# MB_RELAY.net
KiCad netlist of a schematic drawn in Altium Designer
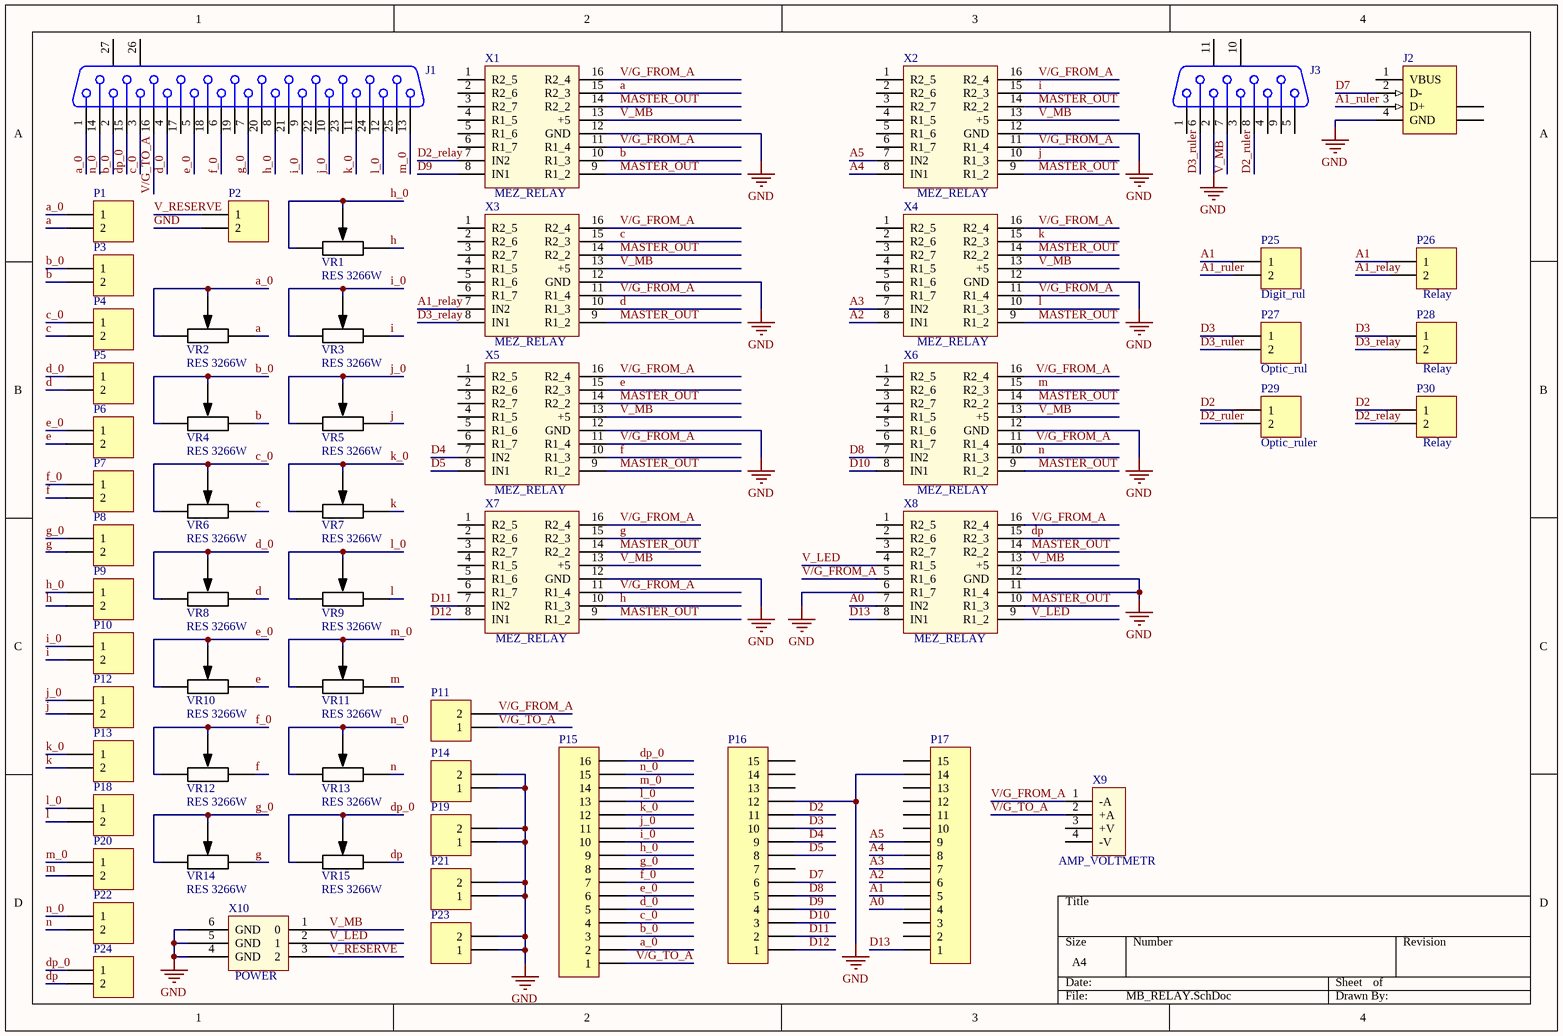
[diagram p0: MB_RELAY.SchDoc]

(export (version "E")
  (design (tool "Eeschema 10.0.6"))
  (components
    (comp (ref "J1")
      (value "D Connector 25")
      (footprint "DSUB1.385-2H25A")
      (description "Receptacle Assembly, 25 Position, Right Angle")
      (fields (field (name "PUBLISHER") "Altium Limited"))
      (libsource (lib "Miscellaneous Connectors") (part "D Connector 25"))
    )
    (comp (ref "J2")
      (value "1-353576-1")
      (footprint "353576")
      (description "USB 1.1, Right Angle, SMT, A Type, Receptacle, 4 Position, White")
      (fields (field (name "PUBLISHER") "Altium Limited"))
      (libsource (lib "AMP Serial Bus USB") (part "1-353576-1"))
    )
    (comp (ref "J3")
      (value "D Connector 9")
      (footprint "DSUB1.385-2H9")
      (description "Receptacle Assembly, 9 Position, Right Angle")
      (fields (field (name "PUBLISHER") "Altium Limited"))
      (libsource (lib "Miscellaneous Connectors") (part "D Connector 9"))
    )
    (comp (ref "P1")
      (value "Header 2")
      (footprint "HDR1X2")
      (description "Header, 2-Pin")
      (fields (field (name "PUBLISHER") "Altium Limited"))
      (libsource (lib "Miscellaneous Connectors") (part "Header 2"))
    )
    (comp (ref "P2")
      (value "Header 2")
      (footprint "HDR1X2")
      (description "Header, 2-Pin")
      (fields (field (name "PUBLISHER") "Altium Limited"))
      (libsource (lib "Miscellaneous Connectors") (part "Header 2"))
    )
    (comp (ref "P3")
      (value "Header 2")
      (footprint "HDR1X2")
      (description "Header, 2-Pin")
      (fields (field (name "PUBLISHER") "Altium Limited"))
      (libsource (lib "Miscellaneous Connectors") (part "Header 2"))
    )
    (comp (ref "P4")
      (value "Header 2")
      (footprint "HDR1X2")
      (description "Header, 2-Pin")
      (fields (field (name "PUBLISHER") "Altium Limited"))
      (libsource (lib "Miscellaneous Connectors") (part "Header 2"))
    )
    (comp (ref "P5")
      (value "Header 2")
      (footprint "HDR1X2")
      (description "Header, 2-Pin")
      (fields (field (name "PUBLISHER") "Altium Limited"))
      (libsource (lib "Miscellaneous Connectors") (part "Header 2"))
    )
    (comp (ref "P6")
      (value "GND")
      (footprint "HDR1X2")
      (description "Header, 2-Pin")
      (fields (field (name "PUBLISHER") "Altium Limited"))
      (libsource (lib "Miscellaneous Connectors") (part "Header 2"))
    )
    (comp (ref "P7")
      (value "GND")
      (footprint "HDR1X2")
      (description "Header, 2-Pin")
      (fields (field (name "PUBLISHER") "Altium Limited"))
      (libsource (lib "Miscellaneous Connectors") (part "Header 2"))
    )
    (comp (ref "P8")
      (value "GND")
      (footprint "HDR1X2")
      (description "Header, 2-Pin")
      (fields (field (name "PUBLISHER") "Altium Limited"))
      (libsource (lib "Miscellaneous Connectors") (part "Header 2"))
    )
    (comp (ref "P9")
      (value "GND")
      (footprint "HDR1X2")
      (description "Header, 2-Pin")
      (fields (field (name "PUBLISHER") "Altium Limited"))
      (libsource (lib "Miscellaneous Connectors") (part "Header 2"))
    )
    (comp (ref "P10")
      (value "Header 2")
      (footprint "HDR1X2")
      (description "Header, 2-Pin")
      (fields (field (name "PUBLISHER") "Altium Limited"))
      (libsource (lib "Miscellaneous Connectors") (part "Header 2"))
    )
    (comp (ref "P11")
      (value "Header 2")
      (footprint "HDR1X2")
      (description "Header, 2-Pin")
      (fields (field (name "PUBLISHER") "Altium Limited"))
      (libsource (lib "") (part "Header 2_1"))
    )
    (comp (ref "P12")
      (value "Header 2")
      (footprint "HDR1X2")
      (description "Header, 2-Pin")
      (fields (field (name "PUBLISHER") "Altium Limited"))
      (libsource (lib "Miscellaneous Connectors") (part "Header 2"))
    )
    (comp (ref "P13")
      (value "GND")
      (footprint "HDR1X2")
      (description "Header, 2-Pin")
      (fields (field (name "PUBLISHER") "Altium Limited"))
      (libsource (lib "Miscellaneous Connectors") (part "Header 2"))
    )
    (comp (ref "P14")
      (value "GND")
      (footprint "HDR1X2")
      (description "Header, 2-Pin")
      (fields (field (name "PUBLISHER") "Altium Limited"))
      (libsource (lib "") (part "Header 2_1"))
    )
    (comp (ref "P15")
      (value "Header 16")
      (footprint "HDR1X16")
      (description "Header, 16-Pin")
      (fields (field (name "PUBLISHER") "Altium Limited"))
      (libsource (lib "Miscellaneous Connectors") (part "Header 16"))
    )
    (comp (ref "P16")
      (value "Header 15")
      (footprint "HDR1X15")
      (description "Header, 15-Pin")
      (fields (field (name "PUBLISHER") "Altium Limited"))
      (libsource (lib "Miscellaneous Connectors") (part "Header 15"))
    )
    (comp (ref "P17")
      (value "Header 15")
      (footprint "HDR1X15")
      (description "Header, 15-Pin")
      (fields (field (name "PUBLISHER") "Altium Limited"))
      (libsource (lib "") (part "Header 15_1"))
    )
    (comp (ref "P18")
      (value "GND")
      (footprint "HDR1X2")
      (description "Header, 2-Pin")
      (fields (field (name "PUBLISHER") "Altium Limited"))
      (libsource (lib "Miscellaneous Connectors") (part "Header 2"))
    )
    (comp (ref "P19")
      (value "GND")
      (footprint "HDR1X2")
      (description "Header, 2-Pin")
      (fields (field (name "PUBLISHER") "Altium Limited"))
      (libsource (lib "") (part "Header 2_1"))
    )
    (comp (ref "P20")
      (value "GND")
      (footprint "HDR1X2")
      (description "Header, 2-Pin")
      (fields (field (name "PUBLISHER") "Altium Limited"))
      (libsource (lib "Miscellaneous Connectors") (part "Header 2"))
    )
    (comp (ref "P21")
      (value "GND")
      (footprint "HDR1X2")
      (description "Header, 2-Pin")
      (fields (field (name "PUBLISHER") "Altium Limited"))
      (libsource (lib "") (part "Header 2_1"))
    )
    (comp (ref "P22")
      (value "GND")
      (footprint "HDR1X2")
      (description "Header, 2-Pin")
      (fields (field (name "PUBLISHER") "Altium Limited"))
      (libsource (lib "Miscellaneous Connectors") (part "Header 2"))
    )
    (comp (ref "P23")
      (value "GND")
      (footprint "HDR1X2")
      (description "Header, 2-Pin")
      (fields (field (name "PUBLISHER") "Altium Limited"))
      (libsource (lib "") (part "Header 2_1"))
    )
    (comp (ref "P24")
      (value "GND")
      (footprint "HDR1X2")
      (description "Header, 2-Pin")
      (fields (field (name "PUBLISHER") "Altium Limited"))
      (libsource (lib "Miscellaneous Connectors") (part "Header 2"))
    )
    (comp (ref "P25")
      (value "Digit_rul")
      (footprint "HDR1X2")
      (description "Header, 2-Pin")
      (fields (field (name "PUBLISHER") "Altium Limited"))
      (libsource (lib "Miscellaneous Connectors") (part "Header 2"))
    )
    (comp (ref "P26")
      (value "Relay")
      (footprint "HDR1X2")
      (description "Header, 2-Pin")
      (fields (field (name "PUBLISHER") "Altium Limited"))
      (libsource (lib "Miscellaneous Connectors") (part "Header 2"))
    )
    (comp (ref "P27")
      (value "Optic_rul")
      (footprint "HDR1X2")
      (description "Header, 2-Pin")
      (fields (field (name "PUBLISHER") "Altium Limited"))
      (libsource (lib "Miscellaneous Connectors") (part "Header 2"))
    )
    (comp (ref "P28")
      (value "Relay")
      (footprint "HDR1X2")
      (description "Header, 2-Pin")
      (fields (field (name "PUBLISHER") "Altium Limited"))
      (libsource (lib "Miscellaneous Connectors") (part "Header 2"))
    )
    (comp (ref "P29")
      (value "Optic_ruler")
      (footprint "HDR1X2")
      (description "Header, 2-Pin")
      (fields (field (name "PUBLISHER") "Altium Limited"))
      (libsource (lib "Miscellaneous Connectors") (part "Header 2"))
    )
    (comp (ref "P30")
      (value "Relay")
      (footprint "HDR1X2")
      (description "Header, 2-Pin")
      (fields (field (name "PUBLISHER") "Altium Limited"))
      (libsource (lib "Miscellaneous Connectors") (part "Header 2"))
    )
    (comp (ref "VR1")
      (value "RES 3266W")
      (footprint "aab_Passive:RES 3266W")
      (libsource (lib "aab_Schlib") (part "RES 3266W"))
    )
    (comp (ref "VR2")
      (value "RES 3266W")
      (footprint "aab_Passive:RES 3266W")
      (libsource (lib "aab_Schlib") (part "RES 3266W"))
    )
    (comp (ref "VR3")
      (value "RES 3266W")
      (footprint "aab_Passive:RES 3266W")
      (libsource (lib "aab_Schlib") (part "RES 3266W"))
    )
    (comp (ref "VR4")
      (value "RES 3266W")
      (footprint "aab_Passive:RES 3266W")
      (libsource (lib "aab_Schlib") (part "RES 3266W"))
    )
    (comp (ref "VR5")
      (value "RES 3266W")
      (footprint "aab_Passive:RES 3266W")
      (libsource (lib "aab_Schlib") (part "RES 3266W"))
    )
    (comp (ref "VR6")
      (value "RES 3266W")
      (footprint "aab_Passive:RES 3266W")
      (libsource (lib "aab_Schlib") (part "RES 3266W"))
    )
    (comp (ref "VR7")
      (value "RES 3266W")
      (footprint "aab_Passive:RES 3266W")
      (libsource (lib "aab_Schlib") (part "RES 3266W"))
    )
    (comp (ref "VR8")
      (value "RES 3266W")
      (footprint "aab_Passive:RES 3266W")
      (libsource (lib "aab_Schlib") (part "RES 3266W"))
    )
    (comp (ref "VR9")
      (value "RES 3266W")
      (footprint "aab_Passive:RES 3266W")
      (libsource (lib "aab_Schlib") (part "RES 3266W"))
    )
    (comp (ref "VR10")
      (value "RES 3266W")
      (footprint "aab_Passive:RES 3266W")
      (libsource (lib "aab_Schlib") (part "RES 3266W"))
    )
    (comp (ref "VR11")
      (value "RES 3266W")
      (footprint "aab_Passive:RES 3266W")
      (libsource (lib "aab_Schlib") (part "RES 3266W"))
    )
    (comp (ref "VR12")
      (value "RES 3266W")
      (footprint "aab_Passive:RES 3266W")
      (libsource (lib "aab_Schlib") (part "RES 3266W"))
    )
    (comp (ref "VR13")
      (value "RES 3266W")
      (footprint "aab_Passive:RES 3266W")
      (libsource (lib "aab_Schlib") (part "RES 3266W"))
    )
    (comp (ref "VR14")
      (value "RES 3266W")
      (footprint "aab_Passive:RES 3266W")
      (libsource (lib "aab_Schlib") (part "RES 3266W"))
    )
    (comp (ref "VR15")
      (value "RES 3266W")
      (footprint "aab_Passive:RES 3266W")
      (libsource (lib "aab_Schlib") (part "RES 3266W"))
    )
    (comp (ref "X1")
      (value "MEZ_RELAY")
      (footprint "MEZ_RELAY")
      (libsource (lib "msp_SchLib") (part "MEZ_RELAY"))
    )
    (comp (ref "X2")
      (value "MEZ_RELAY")
      (footprint "MEZ_RELAY")
      (libsource (lib "msp_SchLib") (part "MEZ_RELAY"))
    )
    (comp (ref "X3")
      (value "MEZ_RELAY")
      (footprint "MEZ_RELAY")
      (libsource (lib "msp_SchLib") (part "MEZ_RELAY"))
    )
    (comp (ref "X4")
      (value "MEZ_RELAY")
      (footprint "MEZ_RELAY")
      (libsource (lib "msp_SchLib") (part "MEZ_RELAY"))
    )
    (comp (ref "X5")
      (value "MEZ_RELAY")
      (footprint "MEZ_RELAY")
      (libsource (lib "msp_SchLib") (part "MEZ_RELAY"))
    )
    (comp (ref "X6")
      (value "MEZ_RELAY")
      (footprint "MEZ_RELAY")
      (libsource (lib "msp_SchLib") (part "MEZ_RELAY"))
    )
    (comp (ref "X7")
      (value "MEZ_RELAY")
      (footprint "MEZ_RELAY")
      (libsource (lib "msp_SchLib") (part "MEZ_RELAY"))
    )
    (comp (ref "X8")
      (value "MEZ_RELAY")
      (footprint "MEZ_RELAY")
      (libsource (lib "msp_SchLib") (part "MEZ_RELAY"))
    )
    (comp (ref "X9")
      (value "AMP_VOLTMETR")
      (footprint "vpl_Passive:AMP_VOLTMETER")
      (libsource (lib "msp_SchLib") (part "AMP_VOLTMETR"))
    )
    (comp (ref "X10")
      (value "POWER")
      (footprint "vpl_Passive:POWER")
      (libsource (lib "msp_SchLib") (part "POWER"))
    )
  )
  (nets
    (net (code "1") (name "/A0") (class "Default")
      (node (ref "P17") (pin "4") (pinfunction "4_4") (pintype "passive"))
      (node (ref "X8") (pin "7") (pinfunction "IN2_7") (pintype "passive"))
    )
    (net (code "2") (name "/A1") (class "Default")
      (node (ref "P17") (pin "5") (pinfunction "5_5") (pintype "passive"))
      (node (ref "P25") (pin "1") (pinfunction "1_1") (pintype "passive"))
      (node (ref "P26") (pin "1") (pinfunction "1_1") (pintype "passive"))
    )
    (net (code "3") (name "/A1_relay") (class "Default")
      (node (ref "P26") (pin "2") (pinfunction "2_2") (pintype "passive"))
      (node (ref "X3") (pin "7") (pinfunction "IN2_7") (pintype "passive"))
    )
    (net (code "4") (name "/A1_ruler") (class "Default")
      (node (ref "J2") (pin "3") (pinfunction "D+_3") (pintype "input"))
      (node (ref "P25") (pin "2") (pinfunction "2_2") (pintype "passive"))
    )
    (net (code "5") (name "/A2") (class "Default")
      (node (ref "P17") (pin "6") (pinfunction "6_6") (pintype "passive"))
      (node (ref "X4") (pin "8") (pinfunction "IN1_8") (pintype "passive"))
    )
    (net (code "6") (name "/A3") (class "Default")
      (node (ref "P17") (pin "7") (pinfunction "7_7") (pintype "passive"))
      (node (ref "X4") (pin "7") (pinfunction "IN2_7") (pintype "passive"))
    )
    (net (code "7") (name "/A4") (class "Default")
      (node (ref "P17") (pin "8") (pinfunction "8_8") (pintype "passive"))
      (node (ref "X2") (pin "8") (pinfunction "IN1_8") (pintype "passive"))
    )
    (net (code "8") (name "/A5") (class "Default")
      (node (ref "P17") (pin "9") (pinfunction "9_9") (pintype "passive"))
      (node (ref "X2") (pin "7") (pinfunction "IN2_7") (pintype "passive"))
    )
    (net (code "9") (name "/D2") (class "Default")
      (node (ref "P16") (pin "11") (pinfunction "11_11") (pintype "passive"))
      (node (ref "P29") (pin "1") (pinfunction "1_1") (pintype "passive"))
      (node (ref "P30") (pin "1") (pinfunction "1_1") (pintype "passive"))
    )
    (net (code "10") (name "/D2_relay") (class "Default")
      (node (ref "P30") (pin "2") (pinfunction "2_2") (pintype "passive"))
      (node (ref "X1") (pin "7") (pinfunction "IN2_7") (pintype "passive"))
    )
    (net (code "11") (name "/D2_ruler") (class "Default")
      (node (ref "J3") (pin "8") (pinfunction "8_8") (pintype "passive"))
      (node (ref "P29") (pin "2") (pinfunction "2_2") (pintype "passive"))
    )
    (net (code "12") (name "/D3") (class "Default")
      (node (ref "P16") (pin "10") (pinfunction "10_10") (pintype "passive"))
      (node (ref "P27") (pin "1") (pinfunction "1_1") (pintype "passive"))
      (node (ref "P28") (pin "1") (pinfunction "1_1") (pintype "passive"))
    )
    (net (code "13") (name "/D3_relay") (class "Default")
      (node (ref "P28") (pin "2") (pinfunction "2_2") (pintype "passive"))
      (node (ref "X3") (pin "8") (pinfunction "IN1_8") (pintype "passive"))
    )
    (net (code "14") (name "/D3_ruler") (class "Default")
      (node (ref "J3") (pin "6") (pinfunction "6_6") (pintype "passive"))
      (node (ref "P27") (pin "2") (pinfunction "2_2") (pintype "passive"))
    )
    (net (code "15") (name "/D4") (class "Default")
      (node (ref "P16") (pin "9") (pinfunction "9_9") (pintype "passive"))
      (node (ref "X5") (pin "7") (pinfunction "IN2_7") (pintype "passive"))
    )
    (net (code "16") (name "/D5") (class "Default")
      (node (ref "P16") (pin "8") (pinfunction "8_8") (pintype "passive"))
      (node (ref "X5") (pin "8") (pinfunction "IN1_8") (pintype "passive"))
    )
    (net (code "17") (name "/D7") (class "Default")
      (node (ref "J2") (pin "2") (pinfunction "D-_2") (pintype "input"))
      (node (ref "P16") (pin "6") (pinfunction "6_6") (pintype "passive"))
    )
    (net (code "18") (name "/D8") (class "Default")
      (node (ref "P16") (pin "5") (pinfunction "5_5") (pintype "passive"))
      (node (ref "X6") (pin "7") (pinfunction "IN2_7") (pintype "passive"))
    )
    (net (code "19") (name "/D9") (class "Default")
      (node (ref "P16") (pin "4") (pinfunction "4_4") (pintype "passive"))
      (node (ref "X1") (pin "8") (pinfunction "IN1_8") (pintype "passive"))
    )
    (net (code "20") (name "/D10") (class "Default")
      (node (ref "P16") (pin "3") (pinfunction "3_3") (pintype "passive"))
      (node (ref "X6") (pin "8") (pinfunction "IN1_8") (pintype "passive"))
    )
    (net (code "21") (name "/D11") (class "Default")
      (node (ref "P16") (pin "2") (pinfunction "2_2") (pintype "passive"))
      (node (ref "X7") (pin "7") (pinfunction "IN2_7") (pintype "passive"))
    )
    (net (code "22") (name "/D12") (class "Default")
      (node (ref "P16") (pin "1") (pinfunction "1_1") (pintype "passive"))
      (node (ref "X7") (pin "8") (pinfunction "IN1_8") (pintype "passive"))
    )
    (net (code "23") (name "/D13") (class "Default")
      (node (ref "P17") (pin "1") (pinfunction "1_1") (pintype "passive"))
      (node (ref "X8") (pin "8") (pinfunction "IN1_8") (pintype "passive"))
    )
    (net (code "24") (name "/MASTER_OUT") (class "Default")
      (node (ref "X1") (pin "14") (pinfunction "R2_2_14") (pintype "passive"))
      (node (ref "X1") (pin "9") (pinfunction "R1_2_9") (pintype "passive"))
      (node (ref "X2") (pin "14") (pinfunction "R2_2_14") (pintype "passive"))
      (node (ref "X2") (pin "9") (pinfunction "R1_2_9") (pintype "passive"))
      (node (ref "X3") (pin "14") (pinfunction "R2_2_14") (pintype "passive"))
      (node (ref "X3") (pin "9") (pinfunction "R1_2_9") (pintype "passive"))
      (node (ref "X4") (pin "14") (pinfunction "R2_2_14") (pintype "passive"))
      (node (ref "X4") (pin "9") (pinfunction "R1_2_9") (pintype "passive"))
      (node (ref "X5") (pin "14") (pinfunction "R2_2_14") (pintype "passive"))
      (node (ref "X5") (pin "9") (pinfunction "R1_2_9") (pintype "passive"))
      (node (ref "X6") (pin "14") (pinfunction "R2_2_14") (pintype "passive"))
      (node (ref "X6") (pin "9") (pinfunction "R1_2_9") (pintype "passive"))
      (node (ref "X7") (pin "14") (pinfunction "R2_2_14") (pintype "passive"))
      (node (ref "X7") (pin "9") (pinfunction "R1_2_9") (pintype "passive"))
      (node (ref "X8") (pin "10") (pinfunction "R1_3_10") (pintype "passive"))
      (node (ref "X8") (pin "14") (pinfunction "R2_2_14") (pintype "passive"))
    )
    (net (code "25") (name "/V_LED") (class "Default")
      (node (ref "X10") (pin "2") (pinfunction "1_2") (pintype "passive"))
      (node (ref "X8") (pin "4") (pinfunction "R1_5_4") (pintype "passive"))
      (node (ref "X8") (pin "9") (pinfunction "R1_2_9") (pintype "passive"))
    )
    (net (code "26") (name "/V_MB") (class "Default")
      (node (ref "J3") (pin "7") (pinfunction "7_7") (pintype "passive"))
      (node (ref "X1") (pin "13") (pinfunction "+5_13") (pintype "passive"))
      (node (ref "X10") (pin "1") (pinfunction "0_1") (pintype "passive"))
      (node (ref "X2") (pin "13") (pinfunction "+5_13") (pintype "passive"))
      (node (ref "X3") (pin "13") (pinfunction "+5_13") (pintype "passive"))
      (node (ref "X4") (pin "13") (pinfunction "+5_13") (pintype "passive"))
      (node (ref "X5") (pin "13") (pinfunction "+5_13") (pintype "passive"))
      (node (ref "X6") (pin "13") (pinfunction "+5_13") (pintype "passive"))
      (node (ref "X7") (pin "13") (pinfunction "+5_13") (pintype "passive"))
      (node (ref "X8") (pin "13") (pinfunction "+5_13") (pintype "passive"))
    )
    (net (code "27") (name "/V_RESERVE") (class "Default")
      (node (ref "P2") (pin "1") (pinfunction "1_1") (pintype "passive"))
      (node (ref "X10") (pin "3") (pinfunction "2_3") (pintype "passive"))
    )
    (net (code "28") (name "/V{slash}G_FROM_A") (class "Default")
      (node (ref "P11") (pin "2") (pinfunction "2_2") (pintype "passive"))
      (node (ref "X1") (pin "11") (pinfunction "R1_4_11") (pintype "passive"))
      (node (ref "X1") (pin "16") (pinfunction "R2_4_16") (pintype "passive"))
      (node (ref "X2") (pin "11") (pinfunction "R1_4_11") (pintype "passive"))
      (node (ref "X2") (pin "16") (pinfunction "R2_4_16") (pintype "passive"))
      (node (ref "X3") (pin "11") (pinfunction "R1_4_11") (pintype "passive"))
      (node (ref "X3") (pin "16") (pinfunction "R2_4_16") (pintype "passive"))
      (node (ref "X4") (pin "11") (pinfunction "R1_4_11") (pintype "passive"))
      (node (ref "X4") (pin "16") (pinfunction "R2_4_16") (pintype "passive"))
      (node (ref "X5") (pin "11") (pinfunction "R1_4_11") (pintype "passive"))
      (node (ref "X5") (pin "16") (pinfunction "R2_4_16") (pintype "passive"))
      (node (ref "X6") (pin "11") (pinfunction "R1_4_11") (pintype "passive"))
      (node (ref "X6") (pin "16") (pinfunction "R2_4_16") (pintype "passive"))
      (node (ref "X7") (pin "11") (pinfunction "R1_4_11") (pintype "passive"))
      (node (ref "X7") (pin "16") (pinfunction "R2_4_16") (pintype "passive"))
      (node (ref "X8") (pin "16") (pinfunction "R2_4_16") (pintype "passive"))
      (node (ref "X8") (pin "5") (pinfunction "R1_6_5") (pintype "passive"))
      (node (ref "X9") (pin "1") (pinfunction "-A_1") (pintype "passive"))
    )
    (net (code "29") (name "/V{slash}G_TO_A") (class "Default")
      (node (ref "J1") (pin "16") (pinfunction "16_16") (pintype "passive"))
      (node (ref "P11") (pin "1") (pinfunction "1_1") (pintype "passive"))
      (node (ref "P15") (pin "1") (pinfunction "1_1") (pintype "passive"))
      (node (ref "X9") (pin "2") (pinfunction "+A_2") (pintype "passive"))
    )
    (net (code "30") (name "/a") (class "Default")
      (node (ref "P1") (pin "2") (pinfunction "2_2") (pintype "passive"))
      (node (ref "VR2") (pin "3") (pinfunction "3_3") (pintype "passive"))
      (node (ref "X1") (pin "15") (pinfunction "R2_3_15") (pintype "passive"))
    )
    (net (code "31") (name "/a_0") (class "Default")
      (node (ref "J1") (pin "1") (pinfunction "1_1") (pintype "passive"))
      (node (ref "P1") (pin "1") (pinfunction "1_1") (pintype "passive"))
      (node (ref "P15") (pin "2") (pinfunction "2_2") (pintype "passive"))
      (node (ref "VR2") (pin "1") (pinfunction "1_1") (pintype "passive"))
      (node (ref "VR2") (pin "2") (pinfunction "2_2") (pintype "passive"))
    )
    (net (code "32") (name "/b") (class "Default")
      (node (ref "P3") (pin "2") (pinfunction "2_2") (pintype "passive"))
      (node (ref "VR4") (pin "3") (pinfunction "3_3") (pintype "passive"))
      (node (ref "X1") (pin "10") (pinfunction "R1_3_10") (pintype "passive"))
    )
    (net (code "33") (name "/b_0") (class "Default")
      (node (ref "J1") (pin "2") (pinfunction "2_2") (pintype "passive"))
      (node (ref "P15") (pin "3") (pinfunction "3_3") (pintype "passive"))
      (node (ref "P3") (pin "1") (pinfunction "1_1") (pintype "passive"))
      (node (ref "VR4") (pin "1") (pinfunction "1_1") (pintype "passive"))
      (node (ref "VR4") (pin "2") (pinfunction "2_2") (pintype "passive"))
    )
    (net (code "34") (name "/c") (class "Default")
      (node (ref "P4") (pin "2") (pinfunction "2_2") (pintype "passive"))
      (node (ref "VR6") (pin "3") (pinfunction "3_3") (pintype "passive"))
      (node (ref "X3") (pin "15") (pinfunction "R2_3_15") (pintype "passive"))
    )
    (net (code "35") (name "/c_0") (class "Default")
      (node (ref "J1") (pin "3") (pinfunction "3_3") (pintype "passive"))
      (node (ref "P15") (pin "4") (pinfunction "4_4") (pintype "passive"))
      (node (ref "P4") (pin "1") (pinfunction "1_1") (pintype "passive"))
      (node (ref "VR6") (pin "1") (pinfunction "1_1") (pintype "passive"))
      (node (ref "VR6") (pin "2") (pinfunction "2_2") (pintype "passive"))
    )
    (net (code "36") (name "/d") (class "Default")
      (node (ref "P5") (pin "2") (pinfunction "2_2") (pintype "passive"))
      (node (ref "VR8") (pin "3") (pinfunction "3_3") (pintype "passive"))
      (node (ref "X3") (pin "10") (pinfunction "R1_3_10") (pintype "passive"))
    )
    (net (code "37") (name "/d_0") (class "Default")
      (node (ref "J1") (pin "4") (pinfunction "4_4") (pintype "passive"))
      (node (ref "P15") (pin "5") (pinfunction "5_5") (pintype "passive"))
      (node (ref "P5") (pin "1") (pinfunction "1_1") (pintype "passive"))
      (node (ref "VR8") (pin "1") (pinfunction "1_1") (pintype "passive"))
      (node (ref "VR8") (pin "2") (pinfunction "2_2") (pintype "passive"))
    )
    (net (code "38") (name "/dp") (class "Default")
      (node (ref "P24") (pin "2") (pinfunction "2_2") (pintype "passive"))
      (node (ref "VR15") (pin "3") (pinfunction "3_3") (pintype "passive"))
      (node (ref "X8") (pin "15") (pinfunction "R2_3_15") (pintype "passive"))
    )
    (net (code "39") (name "/dp_0") (class "Default")
      (node (ref "J1") (pin "15") (pinfunction "15_15") (pintype "passive"))
      (node (ref "P15") (pin "16") (pinfunction "16_16") (pintype "passive"))
      (node (ref "P24") (pin "1") (pinfunction "1_1") (pintype "passive"))
      (node (ref "VR15") (pin "1") (pinfunction "1_1") (pintype "passive"))
      (node (ref "VR15") (pin "2") (pinfunction "2_2") (pintype "passive"))
    )
    (net (code "40") (name "/e") (class "Default")
      (node (ref "P6") (pin "2") (pinfunction "2_2") (pintype "passive"))
      (node (ref "VR10") (pin "3") (pinfunction "3_3") (pintype "passive"))
      (node (ref "X5") (pin "15") (pinfunction "R2_3_15") (pintype "passive"))
    )
    (net (code "41") (name "/e_0") (class "Default")
      (node (ref "J1") (pin "5") (pinfunction "5_5") (pintype "passive"))
      (node (ref "P15") (pin "6") (pinfunction "6_6") (pintype "passive"))
      (node (ref "P6") (pin "1") (pinfunction "1_1") (pintype "passive"))
      (node (ref "VR10") (pin "1") (pinfunction "1_1") (pintype "passive"))
      (node (ref "VR10") (pin "2") (pinfunction "2_2") (pintype "passive"))
    )
    (net (code "42") (name "/f") (class "Default")
      (node (ref "P7") (pin "2") (pinfunction "2_2") (pintype "passive"))
      (node (ref "VR12") (pin "3") (pinfunction "3_3") (pintype "passive"))
      (node (ref "X5") (pin "10") (pinfunction "R1_3_10") (pintype "passive"))
    )
    (net (code "43") (name "/f_0") (class "Default")
      (node (ref "J1") (pin "6") (pinfunction "6_6") (pintype "passive"))
      (node (ref "P15") (pin "7") (pinfunction "7_7") (pintype "passive"))
      (node (ref "P7") (pin "1") (pinfunction "1_1") (pintype "passive"))
      (node (ref "VR12") (pin "1") (pinfunction "1_1") (pintype "passive"))
      (node (ref "VR12") (pin "2") (pinfunction "2_2") (pintype "passive"))
    )
    (net (code "44") (name "/g") (class "Default")
      (node (ref "P8") (pin "2") (pinfunction "2_2") (pintype "passive"))
      (node (ref "VR14") (pin "3") (pinfunction "3_3") (pintype "passive"))
      (node (ref "X7") (pin "15") (pinfunction "R2_3_15") (pintype "passive"))
    )
    (net (code "45") (name "/g_0") (class "Default")
      (node (ref "J1") (pin "7") (pinfunction "7_7") (pintype "passive"))
      (node (ref "P15") (pin "8") (pinfunction "8_8") (pintype "passive"))
      (node (ref "P8") (pin "1") (pinfunction "1_1") (pintype "passive"))
      (node (ref "VR14") (pin "1") (pinfunction "1_1") (pintype "passive"))
      (node (ref "VR14") (pin "2") (pinfunction "2_2") (pintype "passive"))
    )
    (net (code "46") (name "/h") (class "Default")
      (node (ref "P9") (pin "2") (pinfunction "2_2") (pintype "passive"))
      (node (ref "VR1") (pin "3") (pinfunction "3_3") (pintype "passive"))
      (node (ref "X7") (pin "10") (pinfunction "R1_3_10") (pintype "passive"))
    )
    (net (code "47") (name "/h_0") (class "Default")
      (node (ref "J1") (pin "8") (pinfunction "8_8") (pintype "passive"))
      (node (ref "P15") (pin "9") (pinfunction "9_9") (pintype "passive"))
      (node (ref "P9") (pin "1") (pinfunction "1_1") (pintype "passive"))
      (node (ref "VR1") (pin "1") (pinfunction "1_1") (pintype "passive"))
      (node (ref "VR1") (pin "2") (pinfunction "2_2") (pintype "passive"))
    )
    (net (code "48") (name "/i") (class "Default")
      (node (ref "P10") (pin "2") (pinfunction "2_2") (pintype "passive"))
      (node (ref "VR3") (pin "3") (pinfunction "3_3") (pintype "passive"))
      (node (ref "X2") (pin "15") (pinfunction "R2_3_15") (pintype "passive"))
    )
    (net (code "49") (name "/i_0") (class "Default")
      (node (ref "J1") (pin "9") (pinfunction "9_9") (pintype "passive"))
      (node (ref "P10") (pin "1") (pinfunction "1_1") (pintype "passive"))
      (node (ref "P15") (pin "10") (pinfunction "10_10") (pintype "passive"))
      (node (ref "VR3") (pin "1") (pinfunction "1_1") (pintype "passive"))
      (node (ref "VR3") (pin "2") (pinfunction "2_2") (pintype "passive"))
    )
    (net (code "50") (name "/j") (class "Default")
      (node (ref "P12") (pin "2") (pinfunction "2_2") (pintype "passive"))
      (node (ref "VR5") (pin "3") (pinfunction "3_3") (pintype "passive"))
      (node (ref "X2") (pin "10") (pinfunction "R1_3_10") (pintype "passive"))
    )
    (net (code "51") (name "/j_0") (class "Default")
      (node (ref "J1") (pin "10") (pinfunction "10_10") (pintype "passive"))
      (node (ref "P12") (pin "1") (pinfunction "1_1") (pintype "passive"))
      (node (ref "P15") (pin "11") (pinfunction "11_11") (pintype "passive"))
      (node (ref "VR5") (pin "1") (pinfunction "1_1") (pintype "passive"))
      (node (ref "VR5") (pin "2") (pinfunction "2_2") (pintype "passive"))
    )
    (net (code "52") (name "/k") (class "Default")
      (node (ref "P13") (pin "2") (pinfunction "2_2") (pintype "passive"))
      (node (ref "VR7") (pin "3") (pinfunction "3_3") (pintype "passive"))
      (node (ref "X4") (pin "15") (pinfunction "R2_3_15") (pintype "passive"))
    )
    (net (code "53") (name "/k_0") (class "Default")
      (node (ref "J1") (pin "11") (pinfunction "11_11") (pintype "passive"))
      (node (ref "P13") (pin "1") (pinfunction "1_1") (pintype "passive"))
      (node (ref "P15") (pin "12") (pinfunction "12_12") (pintype "passive"))
      (node (ref "VR7") (pin "1") (pinfunction "1_1") (pintype "passive"))
      (node (ref "VR7") (pin "2") (pinfunction "2_2") (pintype "passive"))
    )
    (net (code "54") (name "/l") (class "Default")
      (node (ref "P18") (pin "2") (pinfunction "2_2") (pintype "passive"))
      (node (ref "VR9") (pin "3") (pinfunction "3_3") (pintype "passive"))
      (node (ref "X4") (pin "10") (pinfunction "R1_3_10") (pintype "passive"))
    )
    (net (code "55") (name "/l_0") (class "Default")
      (node (ref "J1") (pin "12") (pinfunction "12_12") (pintype "passive"))
      (node (ref "P15") (pin "13") (pinfunction "13_13") (pintype "passive"))
      (node (ref "P18") (pin "1") (pinfunction "1_1") (pintype "passive"))
      (node (ref "VR9") (pin "1") (pinfunction "1_1") (pintype "passive"))
      (node (ref "VR9") (pin "2") (pinfunction "2_2") (pintype "passive"))
    )
    (net (code "56") (name "/m") (class "Default")
      (node (ref "P20") (pin "2") (pinfunction "2_2") (pintype "passive"))
      (node (ref "VR11") (pin "3") (pinfunction "3_3") (pintype "passive"))
      (node (ref "X6") (pin "15") (pinfunction "R2_3_15") (pintype "passive"))
    )
    (net (code "57") (name "/m_0") (class "Default")
      (node (ref "J1") (pin "13") (pinfunction "13_13") (pintype "passive"))
      (node (ref "P15") (pin "14") (pinfunction "14_14") (pintype "passive"))
      (node (ref "P20") (pin "1") (pinfunction "1_1") (pintype "passive"))
      (node (ref "VR11") (pin "1") (pinfunction "1_1") (pintype "passive"))
      (node (ref "VR11") (pin "2") (pinfunction "2_2") (pintype "passive"))
    )
    (net (code "58") (name "/n") (class "Default")
      (node (ref "P22") (pin "2") (pinfunction "2_2") (pintype "passive"))
      (node (ref "VR13") (pin "3") (pinfunction "3_3") (pintype "passive"))
      (node (ref "X6") (pin "10") (pinfunction "R1_3_10") (pintype "passive"))
    )
    (net (code "59") (name "/n_0") (class "Default")
      (node (ref "J1") (pin "14") (pinfunction "14_14") (pintype "passive"))
      (node (ref "P15") (pin "15") (pinfunction "15_15") (pintype "passive"))
      (node (ref "P22") (pin "1") (pinfunction "1_1") (pintype "passive"))
      (node (ref "VR13") (pin "1") (pinfunction "1_1") (pintype "passive"))
      (node (ref "VR13") (pin "2") (pinfunction "2_2") (pintype "passive"))
    )
    (net (code "60") (name "GND") (class "Default")
      (node (ref "J2") (pin "4") (pinfunction "GND_4") (pintype "power_in"))
      (node (ref "J3") (pin "2") (pinfunction "2_2") (pintype "passive"))
      (node (ref "P14") (pin "1") (pinfunction "1_1") (pintype "passive"))
      (node (ref "P14") (pin "2") (pinfunction "2_2") (pintype "passive"))
      (node (ref "P16") (pin "12") (pinfunction "12_12") (pintype "passive"))
      (node (ref "P17") (pin "14") (pinfunction "14_14") (pintype "passive"))
      (node (ref "P19") (pin "1") (pinfunction "1_1") (pintype "passive"))
      (node (ref "P19") (pin "2") (pinfunction "2_2") (pintype "passive"))
      (node (ref "P2") (pin "2") (pinfunction "2_2") (pintype "passive"))
      (node (ref "P21") (pin "1") (pinfunction "1_1") (pintype "passive"))
      (node (ref "P21") (pin "2") (pinfunction "2_2") (pintype "passive"))
      (node (ref "P23") (pin "1") (pinfunction "1_1") (pintype "passive"))
      (node (ref "P23") (pin "2") (pinfunction "2_2") (pintype "passive"))
      (node (ref "X1") (pin "12") (pinfunction "GND_12") (pintype "passive"))
      (node (ref "X10") (pin "4") (pinfunction "GND_4") (pintype "passive"))
      (node (ref "X10") (pin "5") (pinfunction "GND_5") (pintype "passive"))
      (node (ref "X10") (pin "6") (pinfunction "GND_6") (pintype "passive"))
      (node (ref "X2") (pin "12") (pinfunction "GND_12") (pintype "passive"))
      (node (ref "X3") (pin "12") (pinfunction "GND_12") (pintype "passive"))
      (node (ref "X4") (pin "12") (pinfunction "GND_12") (pintype "passive"))
      (node (ref "X5") (pin "12") (pinfunction "GND_12") (pintype "passive"))
      (node (ref "X6") (pin "12") (pinfunction "GND_12") (pintype "passive"))
      (node (ref "X7") (pin "12") (pinfunction "GND_12") (pintype "passive"))
      (node (ref "X8") (pin "11") (pinfunction "R1_4_11") (pintype "passive"))
      (node (ref "X8") (pin "12") (pinfunction "GND_12") (pintype "passive"))
      (node (ref "X8") (pin "6") (pinfunction "R1_7_6") (pintype "passive"))
    )
    (net (code "61") (name "unconnected-(J1-MH1-Pad26)") (class "Default")
      (node (ref "J1") (pin "26") (pinfunction "MH1_26") (pintype "passive"))
    )
    (net (code "62") (name "unconnected-(J1-MH2-Pad27)") (class "Default")
      (node (ref "J1") (pin "27") (pinfunction "MH2_27") (pintype "passive"))
    )
    (net (code "63") (name "unconnected-(J1-Pad17)") (class "Default")
      (node (ref "J1") (pin "17") (pinfunction "17_17") (pintype "passive"))
    )
    (net (code "64") (name "unconnected-(J1-Pad18)") (class "Default")
      (node (ref "J1") (pin "18") (pinfunction "18_18") (pintype "passive"))
    )
    (net (code "65") (name "unconnected-(J1-Pad19)") (class "Default")
      (node (ref "J1") (pin "19") (pinfunction "19_19") (pintype "passive"))
    )
    (net (code "66") (name "unconnected-(J1-Pad20)") (class "Default")
      (node (ref "J1") (pin "20") (pinfunction "20_20") (pintype "passive"))
    )
    (net (code "67") (name "unconnected-(J1-Pad21)") (class "Default")
      (node (ref "J1") (pin "21") (pinfunction "21_21") (pintype "passive"))
    )
    (net (code "68") (name "unconnected-(J1-Pad22)") (class "Default")
      (node (ref "J1") (pin "22") (pinfunction "22_22") (pintype "passive"))
    )
    (net (code "69") (name "unconnected-(J1-Pad23)") (class "Default")
      (node (ref "J1") (pin "23") (pinfunction "23_23") (pintype "passive"))
    )
    (net (code "70") (name "unconnected-(J1-Pad24)") (class "Default")
      (node (ref "J1") (pin "24") (pinfunction "24_24") (pintype "passive"))
    )
    (net (code "71") (name "unconnected-(J1-Pad25)") (class "Default")
      (node (ref "J1") (pin "25") (pinfunction "25_25") (pintype "passive"))
    )
    (net (code "72") (name "unconnected-(J2-SHLD-Pad5)") (class "Default")
      (node (ref "J2") (pin "5") (pinfunction "SHLD_5") (pintype "passive"))
    )
    (net (code "73") (name "unconnected-(J2-SHLD-Pad6)") (class "Default")
      (node (ref "J2") (pin "6") (pinfunction "SHLD_6") (pintype "passive"))
    )
    (net (code "74") (name "unconnected-(J2-VBUS-Pad1)") (class "Default")
      (node (ref "J2") (pin "1") (pinfunction "VBUS_1") (pintype "power_in"))
    )
    (net (code "75") (name "unconnected-(J3-MH1-Pad10)") (class "Default")
      (node (ref "J3") (pin "10") (pinfunction "MH1_10") (pintype "passive"))
    )
    (net (code "76") (name "unconnected-(J3-MH2-Pad11)") (class "Default")
      (node (ref "J3") (pin "11") (pinfunction "MH2_11") (pintype "passive"))
    )
    (net (code "77") (name "unconnected-(J3-Pad1)") (class "Default")
      (node (ref "J3") (pin "1") (pinfunction "1_1") (pintype "passive"))
    )
    (net (code "78") (name "unconnected-(J3-Pad3)") (class "Default")
      (node (ref "J3") (pin "3") (pinfunction "3_3") (pintype "passive"))
    )
    (net (code "79") (name "unconnected-(J3-Pad4)") (class "Default")
      (node (ref "J3") (pin "4") (pinfunction "4_4") (pintype "passive"))
    )
    (net (code "80") (name "unconnected-(J3-Pad5)") (class "Default")
      (node (ref "J3") (pin "5") (pinfunction "5_5") (pintype "passive"))
    )
    (net (code "81") (name "unconnected-(J3-Pad9)") (class "Default")
      (node (ref "J3") (pin "9") (pinfunction "9_9") (pintype "passive"))
    )
    (net (code "82") (name "unconnected-(P16-Pad7)") (class "Default")
      (node (ref "P16") (pin "7") (pinfunction "7_7") (pintype "passive"))
    )
    (net (code "83") (name "unconnected-(P16-Pad13)") (class "Default")
      (node (ref "P16") (pin "13") (pinfunction "13_13") (pintype "passive"))
    )
    (net (code "84") (name "unconnected-(P16-Pad14)") (class "Default")
      (node (ref "P16") (pin "14") (pinfunction "14_14") (pintype "passive"))
    )
    (net (code "85") (name "unconnected-(P16-Pad15)") (class "Default")
      (node (ref "P16") (pin "15") (pinfunction "15_15") (pintype "passive"))
    )
    (net (code "86") (name "unconnected-(P17-Pad2)") (class "Default")
      (node (ref "P17") (pin "2") (pinfunction "2_2") (pintype "passive"))
    )
    (net (code "87") (name "unconnected-(P17-Pad3)") (class "Default")
      (node (ref "P17") (pin "3") (pinfunction "3_3") (pintype "passive"))
    )
    (net (code "88") (name "unconnected-(P17-Pad10)") (class "Default")
      (node (ref "P17") (pin "10") (pinfunction "10_10") (pintype "passive"))
    )
    (net (code "89") (name "unconnected-(P17-Pad11)") (class "Default")
      (node (ref "P17") (pin "11") (pinfunction "11_11") (pintype "passive"))
    )
    (net (code "90") (name "unconnected-(P17-Pad12)") (class "Default")
      (node (ref "P17") (pin "12") (pinfunction "12_12") (pintype "passive"))
    )
    (net (code "91") (name "unconnected-(P17-Pad13)") (class "Default")
      (node (ref "P17") (pin "13") (pinfunction "13_13") (pintype "passive"))
    )
    (net (code "92") (name "unconnected-(P17-Pad15)") (class "Default")
      (node (ref "P17") (pin "15") (pinfunction "15_15") (pintype "passive"))
    )
    (net (code "93") (name "unconnected-(X1-R1_5-Pad4)") (class "Default")
      (node (ref "X1") (pin "4") (pinfunction "R1_5_4") (pintype "passive"))
    )
    (net (code "94") (name "unconnected-(X1-R1_6-Pad5)") (class "Default")
      (node (ref "X1") (pin "5") (pinfunction "R1_6_5") (pintype "passive"))
    )
    (net (code "95") (name "unconnected-(X1-R1_7-Pad6)") (class "Default")
      (node (ref "X1") (pin "6") (pinfunction "R1_7_6") (pintype "passive"))
    )
    (net (code "96") (name "unconnected-(X1-R2_5-Pad1)") (class "Default")
      (node (ref "X1") (pin "1") (pinfunction "R2_5_1") (pintype "passive"))
    )
    (net (code "97") (name "unconnected-(X1-R2_6-Pad2)") (class "Default")
      (node (ref "X1") (pin "2") (pinfunction "R2_6_2") (pintype "passive"))
    )
    (net (code "98") (name "unconnected-(X1-R2_7-Pad3)") (class "Default")
      (node (ref "X1") (pin "3") (pinfunction "R2_7_3") (pintype "passive"))
    )
    (net (code "99") (name "unconnected-(X2-R1_5-Pad4)") (class "Default")
      (node (ref "X2") (pin "4") (pinfunction "R1_5_4") (pintype "passive"))
    )
    (net (code "100") (name "unconnected-(X2-R1_6-Pad5)") (class "Default")
      (node (ref "X2") (pin "5") (pinfunction "R1_6_5") (pintype "passive"))
    )
    (net (code "101") (name "unconnected-(X2-R1_7-Pad6)") (class "Default")
      (node (ref "X2") (pin "6") (pinfunction "R1_7_6") (pintype "passive"))
    )
    (net (code "102") (name "unconnected-(X2-R2_5-Pad1)") (class "Default")
      (node (ref "X2") (pin "1") (pinfunction "R2_5_1") (pintype "passive"))
    )
    (net (code "103") (name "unconnected-(X2-R2_6-Pad2)") (class "Default")
      (node (ref "X2") (pin "2") (pinfunction "R2_6_2") (pintype "passive"))
    )
    (net (code "104") (name "unconnected-(X2-R2_7-Pad3)") (class "Default")
      (node (ref "X2") (pin "3") (pinfunction "R2_7_3") (pintype "passive"))
    )
    (net (code "105") (name "unconnected-(X3-R1_5-Pad4)") (class "Default")
      (node (ref "X3") (pin "4") (pinfunction "R1_5_4") (pintype "passive"))
    )
    (net (code "106") (name "unconnected-(X3-R1_6-Pad5)") (class "Default")
      (node (ref "X3") (pin "5") (pinfunction "R1_6_5") (pintype "passive"))
    )
    (net (code "107") (name "unconnected-(X3-R1_7-Pad6)") (class "Default")
      (node (ref "X3") (pin "6") (pinfunction "R1_7_6") (pintype "passive"))
    )
    (net (code "108") (name "unconnected-(X3-R2_5-Pad1)") (class "Default")
      (node (ref "X3") (pin "1") (pinfunction "R2_5_1") (pintype "passive"))
    )
    (net (code "109") (name "unconnected-(X3-R2_6-Pad2)") (class "Default")
      (node (ref "X3") (pin "2") (pinfunction "R2_6_2") (pintype "passive"))
    )
    (net (code "110") (name "unconnected-(X3-R2_7-Pad3)") (class "Default")
      (node (ref "X3") (pin "3") (pinfunction "R2_7_3") (pintype "passive"))
    )
    (net (code "111") (name "unconnected-(X4-R1_5-Pad4)") (class "Default")
      (node (ref "X4") (pin "4") (pinfunction "R1_5_4") (pintype "passive"))
    )
    (net (code "112") (name "unconnected-(X4-R1_6-Pad5)") (class "Default")
      (node (ref "X4") (pin "5") (pinfunction "R1_6_5") (pintype "passive"))
    )
    (net (code "113") (name "unconnected-(X4-R1_7-Pad6)") (class "Default")
      (node (ref "X4") (pin "6") (pinfunction "R1_7_6") (pintype "passive"))
    )
    (net (code "114") (name "unconnected-(X4-R2_5-Pad1)") (class "Default")
      (node (ref "X4") (pin "1") (pinfunction "R2_5_1") (pintype "passive"))
    )
    (net (code "115") (name "unconnected-(X4-R2_6-Pad2)") (class "Default")
      (node (ref "X4") (pin "2") (pinfunction "R2_6_2") (pintype "passive"))
    )
    (net (code "116") (name "unconnected-(X4-R2_7-Pad3)") (class "Default")
      (node (ref "X4") (pin "3") (pinfunction "R2_7_3") (pintype "passive"))
    )
    (net (code "117") (name "unconnected-(X5-R1_5-Pad4)") (class "Default")
      (node (ref "X5") (pin "4") (pinfunction "R1_5_4") (pintype "passive"))
    )
    (net (code "118") (name "unconnected-(X5-R1_6-Pad5)") (class "Default")
      (node (ref "X5") (pin "5") (pinfunction "R1_6_5") (pintype "passive"))
    )
    (net (code "119") (name "unconnected-(X5-R1_7-Pad6)") (class "Default")
      (node (ref "X5") (pin "6") (pinfunction "R1_7_6") (pintype "passive"))
    )
    (net (code "120") (name "unconnected-(X5-R2_5-Pad1)") (class "Default")
      (node (ref "X5") (pin "1") (pinfunction "R2_5_1") (pintype "passive"))
    )
    (net (code "121") (name "unconnected-(X5-R2_6-Pad2)") (class "Default")
      (node (ref "X5") (pin "2") (pinfunction "R2_6_2") (pintype "passive"))
    )
    (net (code "122") (name "unconnected-(X5-R2_7-Pad3)") (class "Default")
      (node (ref "X5") (pin "3") (pinfunction "R2_7_3") (pintype "passive"))
    )
    (net (code "123") (name "unconnected-(X6-R1_5-Pad4)") (class "Default")
      (node (ref "X6") (pin "4") (pinfunction "R1_5_4") (pintype "passive"))
    )
    (net (code "124") (name "unconnected-(X6-R1_6-Pad5)") (class "Default")
      (node (ref "X6") (pin "5") (pinfunction "R1_6_5") (pintype "passive"))
    )
    (net (code "125") (name "unconnected-(X6-R1_7-Pad6)") (class "Default")
      (node (ref "X6") (pin "6") (pinfunction "R1_7_6") (pintype "passive"))
    )
    (net (code "126") (name "unconnected-(X6-R2_5-Pad1)") (class "Default")
      (node (ref "X6") (pin "1") (pinfunction "R2_5_1") (pintype "passive"))
    )
    (net (code "127") (name "unconnected-(X6-R2_6-Pad2)") (class "Default")
      (node (ref "X6") (pin "2") (pinfunction "R2_6_2") (pintype "passive"))
    )
    (net (code "128") (name "unconnected-(X6-R2_7-Pad3)") (class "Default")
      (node (ref "X6") (pin "3") (pinfunction "R2_7_3") (pintype "passive"))
    )
    (net (code "129") (name "unconnected-(X7-R1_5-Pad4)") (class "Default")
      (node (ref "X7") (pin "4") (pinfunction "R1_5_4") (pintype "passive"))
    )
    (net (code "130") (name "unconnected-(X7-R1_6-Pad5)") (class "Default")
      (node (ref "X7") (pin "5") (pinfunction "R1_6_5") (pintype "passive"))
    )
    (net (code "131") (name "unconnected-(X7-R1_7-Pad6)") (class "Default")
      (node (ref "X7") (pin "6") (pinfunction "R1_7_6") (pintype "passive"))
    )
    (net (code "132") (name "unconnected-(X7-R2_5-Pad1)") (class "Default")
      (node (ref "X7") (pin "1") (pinfunction "R2_5_1") (pintype "passive"))
    )
    (net (code "133") (name "unconnected-(X7-R2_6-Pad2)") (class "Default")
      (node (ref "X7") (pin "2") (pinfunction "R2_6_2") (pintype "passive"))
    )
    (net (code "134") (name "unconnected-(X7-R2_7-Pad3)") (class "Default")
      (node (ref "X7") (pin "3") (pinfunction "R2_7_3") (pintype "passive"))
    )
    (net (code "135") (name "unconnected-(X8-R2_5-Pad1)") (class "Default")
      (node (ref "X8") (pin "1") (pinfunction "R2_5_1") (pintype "passive"))
    )
    (net (code "136") (name "unconnected-(X8-R2_6-Pad2)") (class "Default")
      (node (ref "X8") (pin "2") (pinfunction "R2_6_2") (pintype "passive"))
    )
    (net (code "137") (name "unconnected-(X8-R2_7-Pad3)") (class "Default")
      (node (ref "X8") (pin "3") (pinfunction "R2_7_3") (pintype "passive"))
    )
    (net (code "138") (name "unconnected-(X9-+V-Pad3)") (class "Default")
      (node (ref "X9") (pin "3") (pinfunction "+V_3") (pintype "passive"))
    )
    (net (code "139") (name "unconnected-(X9--V-Pad4)") (class "Default")
      (node (ref "X9") (pin "4") (pinfunction "-V_4") (pintype "passive"))
    )
  )
)
